# schematicEagle.net
KiCad netlist of a schematic drawn in EAGLE
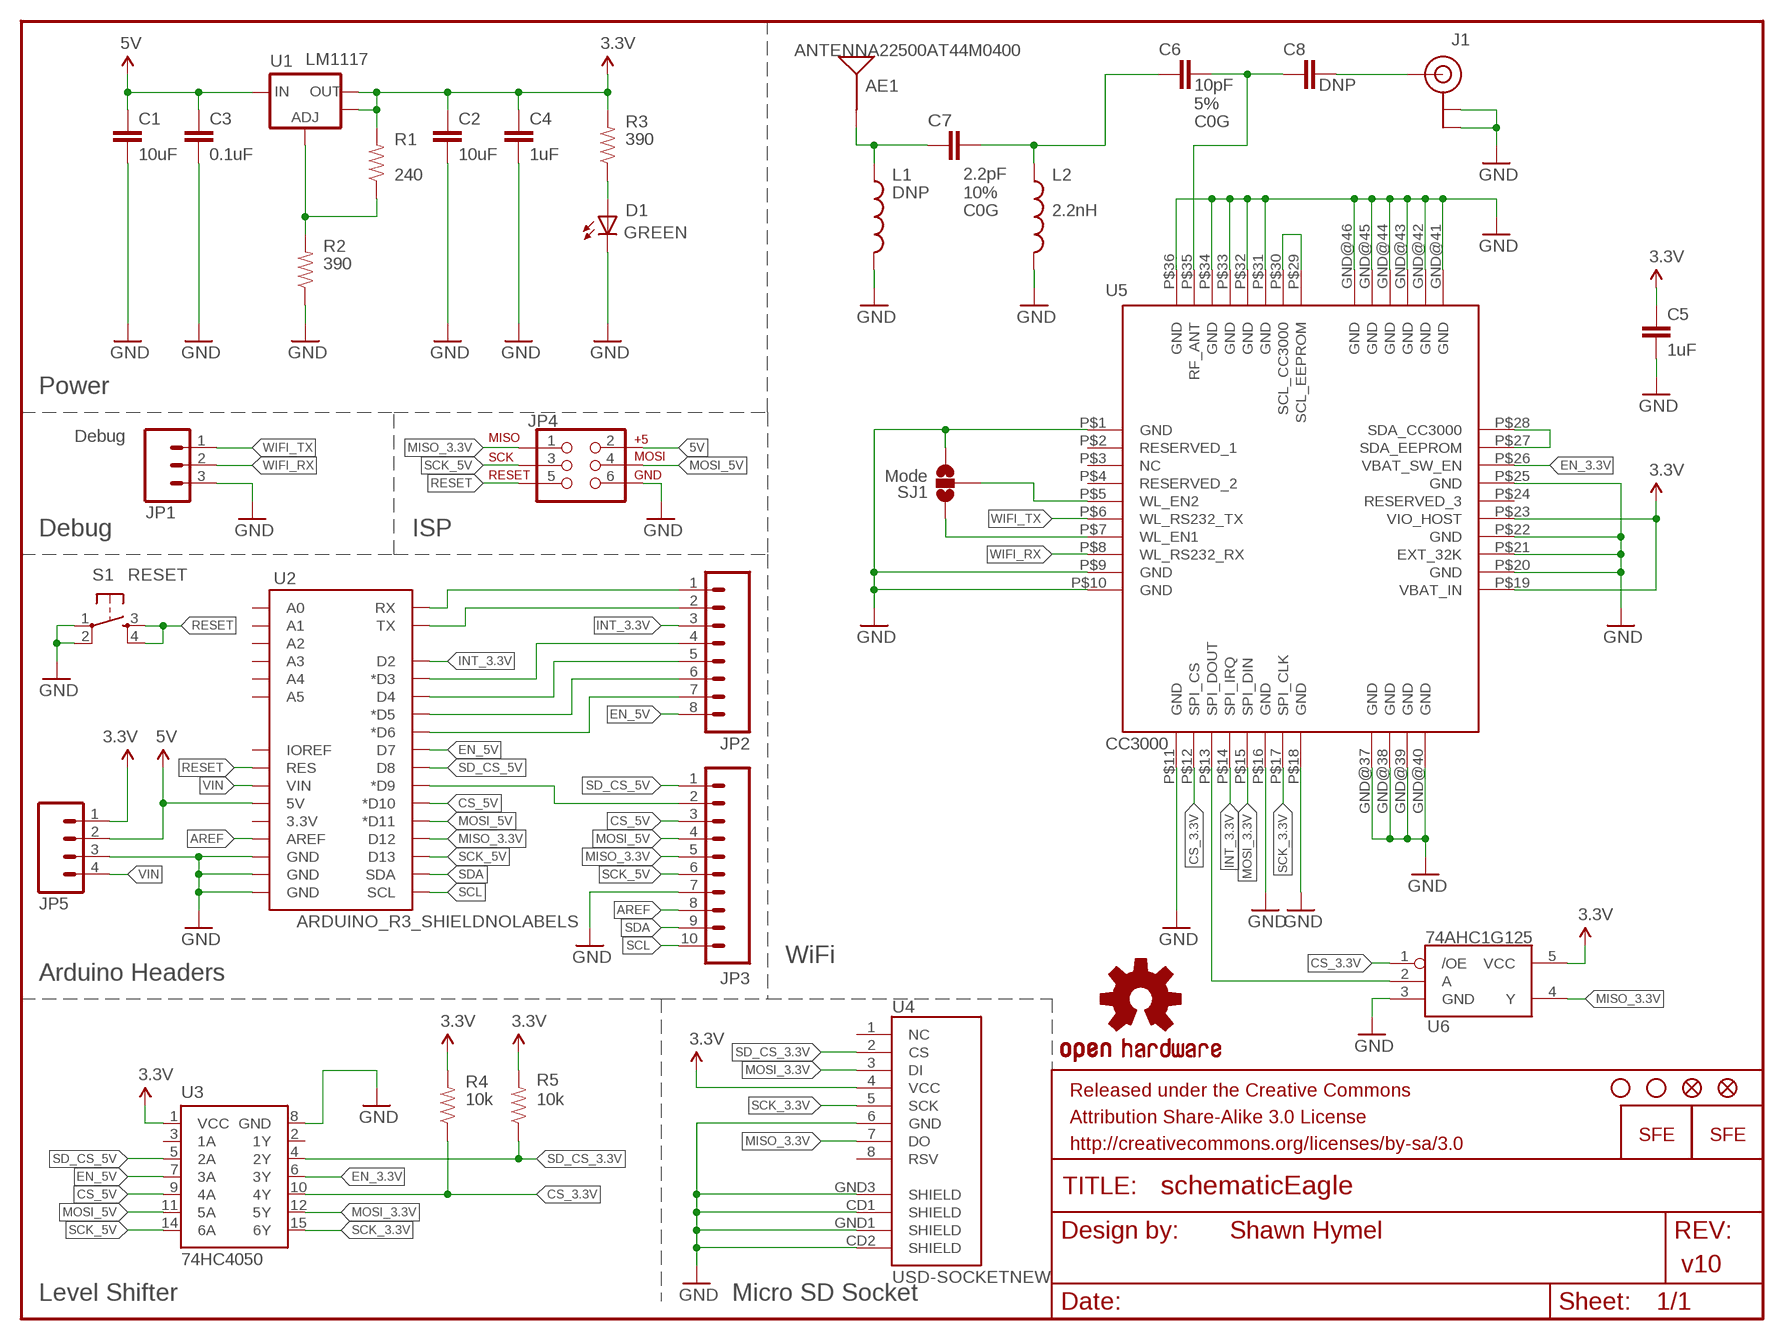
[diagram p0: schematic, sheet 1]

(export (version "E")
  (design (tool "Eeschema 10.0.6"))
  (components
    (comp (ref "AE1")
      (value "ANTENNA22500AT44M0400")
      (footprint "eagle-import:ANTENNA-CHIP_2500AT44M0400")
      (libsource (lib "eagle-import") (part "ANTENNA22500AT44M0400"))
    )
    (comp (ref "C1")
      (value "10uF")
      (footprint "eagle-import:0805")
      (libsource (lib "eagle-import") (part "CAP0805"))
    )
    (comp (ref "C2")
      (value "10uF")
      (footprint "eagle-import:0805")
      (libsource (lib "eagle-import") (part "CAP0805"))
    )
    (comp (ref "C3")
      (value "0.1uF")
      (footprint "eagle-import:0603-CAP")
      (libsource (lib "eagle-import") (part "CAP0603-CAP"))
    )
    (comp (ref "C4")
      (value "1uF")
      (footprint "eagle-import:0805")
      (libsource (lib "eagle-import") (part "CAP0805"))
    )
    (comp (ref "C5")
      (value "1uF")
      (footprint "eagle-import:0805")
      (libsource (lib "eagle-import") (part "CAP0805"))
    )
    (comp (ref "C6")
      (value "10pF")
      (footprint "eagle-import:0603-CAP")
      (fields (field (name "COEFF") "C0G") (field (name "TOL") "5%"))
      (libsource (lib "eagle-import") (part "CAP0603-CAP"))
    )
    (comp (ref "C7")
      (value "2.2pF")
      (footprint "eagle-import:0603-CAP")
      (fields (field (name "COEFF") "C0G") (field (name "TOL") "10%"))
      (libsource (lib "eagle-import") (part "CAP0603-CAP"))
    )
    (comp (ref "C8")
      (value "DNP")
      (footprint "eagle-import:0603-CAP")
      (libsource (lib "eagle-import") (part "CAP0603-CAP"))
    )
    (comp (ref "D1")
      (value "GREEN")
      (footprint "eagle-import:LED-0603")
      (libsource (lib "eagle-import") (part "LED-GREEN0603"))
    )
    (comp (ref "FID1")
      (value "FIDUCIAL1X2")
      (footprint "eagle-import:FIDUCIAL-1X2")
      (libsource (lib "eagle-import") (part "FIDUCIAL1X2"))
    )
    (comp (ref "FID2")
      (value "FIDUCIAL1X2")
      (footprint "eagle-import:FIDUCIAL-1X2")
      (libsource (lib "eagle-import") (part "FIDUCIAL1X2"))
    )
    (comp (ref "FRAME1")
      (value "FRAME-LETTER")
      (footprint "eagle-import:CREATIVE_COMMONS")
      (libsource (lib "eagle-import") (part "FRAME-LETTER"))
    )
    (comp (ref "J1")
      (value "U.FL")
      (footprint "eagle-import:U.FL")
      (libsource (lib "eagle-import") (part "U.FL"))
    )
    (comp (ref "JP1")
      (value "Debug")
      (footprint "eagle-import:1X03")
      (libsource (lib "eagle-import") (part "M03PTH"))
    )
    (comp (ref "JP2")
      (value "M08NO_SILK")
      (footprint "eagle-import:1X08_NO_SILK")
      (libsource (lib "eagle-import") (part "M08NO_SILK"))
    )
    (comp (ref "JP3")
      (value "M10NO_SILK")
      (footprint "eagle-import:1X10_NO_SILK")
      (libsource (lib "eagle-import") (part "M10NO_SILK"))
    )
    (comp (ref "JP4")
      (value "AVR_SPI_PRG_6PTH")
      (footprint "eagle-import:2X3")
      (libsource (lib "eagle-import") (part "AVR_SPI_PRG_6PTH"))
    )
    (comp (ref "JP5")
      (value "M04PTH")
      (footprint "eagle-import:1X04")
      (libsource (lib "eagle-import") (part "M04PTH"))
    )
    (comp (ref "L1")
      (value "DNP")
      (footprint "eagle-import:0603")
      (libsource (lib "eagle-import") (part "INDUCTOR0603"))
    )
    (comp (ref "L2")
      (value "2.2nH")
      (footprint "eagle-import:0603")
      (libsource (lib "eagle-import") (part "INDUCTOR0603"))
    )
    (comp (ref "LOGO1")
      (value "OSHW-LOGOS")
      (footprint "eagle-import:OSHW-LOGO-S")
      (libsource (lib "eagle-import") (part "OSHW-LOGOS"))
    )
    (comp (ref "LOGO2")
      (value "LOGO-SFENEW")
      (footprint "eagle-import:SFE-NEW-WEBLOGO")
      (libsource (lib "eagle-import") (part "LOGO-SFENEW"))
    )
    (comp (ref "LOGO3")
      (value "LOGO-SFESK")
      (footprint "eagle-import:SFE-LOGO-FLAME")
      (libsource (lib "eagle-import") (part "LOGO-SFESK"))
    )
    (comp (ref "R1")
      (value "240")
      (footprint "eagle-import:0603-RES")
      (libsource (lib "eagle-import") (part "RESISTOR0603"))
    )
    (comp (ref "R2")
      (value "390")
      (footprint "eagle-import:0603-RES")
      (libsource (lib "eagle-import") (part "RESISTOR0603"))
    )
    (comp (ref "R3")
      (value "390")
      (footprint "eagle-import:0603-RES")
      (libsource (lib "eagle-import") (part "RESISTOR0603-RES"))
    )
    (comp (ref "R4")
      (value "10k")
      (footprint "eagle-import:0603-RES")
      (libsource (lib "eagle-import") (part "RESISTOR0603-RES"))
    )
    (comp (ref "R5")
      (value "10k")
      (footprint "eagle-import:0603-RES")
      (libsource (lib "eagle-import") (part "RESISTOR0603-RES"))
    )
    (comp (ref "S1")
      (value "RESET")
      (footprint "eagle-import:TACTILE_SWITCH_SMD")
      (libsource (lib "eagle-import") (part "TAC_SWITCHSMD"))
    )
    (comp (ref "SJ1")
      (value "Mode")
      (footprint "eagle-import:SJ_3_PASTE1&2")
      (libsource (lib "eagle-import") (part "SOLDERJUMPER_2WAYPASTE1&2"))
    )
    (comp (ref "STANDOFF1")
      (value "STAND-OFF")
      (footprint "eagle-import:STAND-OFF")
      (libsource (lib "eagle-import") (part "STAND-OFF"))
    )
    (comp (ref "STANDOFF2")
      (value "STAND-OFF")
      (footprint "eagle-import:STAND-OFF")
      (libsource (lib "eagle-import") (part "STAND-OFF"))
    )
    (comp (ref "U1")
      (value "LM1117")
      (footprint "eagle-import:SOT223")
      (libsource (lib "eagle-import") (part "V_REG_LM1117SOT223"))
    )
    (comp (ref "U2")
      (value "ARDUINO_R3_SHIELDNOLABELS")
      (footprint "eagle-import:UNO_R3_SHIELD_NOLABELS")
      (libsource (lib "eagle-import") (part "ARDUINO_R3_SHIELDNOLABELS"))
    )
    (comp (ref "U3")
      (value "74HC4050")
      (footprint "eagle-import:SO016")
      (libsource (lib "eagle-import") (part "HEX_CONVERTER"))
    )
    (comp (ref "U4")
      (value "USD-SOCKETNEW")
      (footprint "eagle-import:MICRO-SD-SOCKET-PP")
      (libsource (lib "eagle-import") (part "USD-SOCKETNEW"))
    )
    (comp (ref "U5")
      (value "CC3000")
      (footprint "eagle-import:QFN-46_CC3000")
      (libsource (lib "eagle-import") (part "CC3000"))
    )
    (comp (ref "U6")
      (value "74AHC1G125")
      (footprint "eagle-import:SOT23-5")
      (libsource (lib "eagle-import") (part "74AHC1G125"))
    )
  )
  (nets
    (net (code "1") (name "3.3V") (class "Default")
      (node (ref "C2") (pin "1") (pinfunction "1_1") (pintype "passive"))
      (node (ref "C4") (pin "1") (pinfunction "1_1") (pintype "passive"))
      (node (ref "C5") (pin "1") (pinfunction "1_1") (pintype "passive"))
      (node (ref "JP5") (pin "1") (pinfunction "1_1") (pintype "passive"))
      (node (ref "R1") (pin "2") (pinfunction "2_2") (pintype "passive"))
      (node (ref "R3") (pin "2") (pinfunction "2_2") (pintype "passive"))
      (node (ref "R4") (pin "2") (pinfunction "2_2") (pintype "passive"))
      (node (ref "R5") (pin "2") (pinfunction "2_2") (pintype "passive"))
      (node (ref "U1") (pin "2") (pinfunction "OUT_2") (pintype "output"))
      (node (ref "U1") (pin "4") (pinfunction "OUT_4") (pintype "output"))
      (node (ref "U3") (pin "1") (pinfunction "VCC_1") (pintype "bidirectional"))
      (node (ref "U4") (pin "4") (pinfunction "VCC_4") (pintype "bidirectional"))
      (node (ref "U5") (pin "P$19") (pinfunction "VBAT_IN_P$19") (pintype "bidirectional"))
      (node (ref "U5") (pin "P$23") (pinfunction "VIO_HOST_P$23") (pintype "bidirectional"))
      (node (ref "U6") (pin "5") (pinfunction "VCC_5") (pintype "bidirectional"))
    )
    (net (code "2") (name "5V") (class "Default")
      (node (ref "C1") (pin "1") (pinfunction "1_1") (pintype "passive"))
      (node (ref "C3") (pin "1") (pinfunction "1_1") (pintype "passive"))
      (node (ref "JP4") (pin "2") (pinfunction "2_2") (pintype "passive"))
      (node (ref "JP5") (pin "2") (pinfunction "2_2") (pintype "passive"))
      (node (ref "U1") (pin "3") (pinfunction "IN_3") (pintype "input"))
      (node (ref "U2") (pin "5V") (pinfunction "5V_5V") (pintype "bidirectional"))
    )
    (net (code "3") (name "AREF") (class "Default")
      (node (ref "JP3") (pin "8") (pinfunction "8_8") (pintype "passive"))
      (node (ref "U2") (pin "AREF") (pinfunction "AREF_AREF") (pintype "bidirectional"))
    )
    (net (code "4") (name "CS_3.3V") (class "Default")
      (node (ref "R4") (pin "1") (pinfunction "1_1") (pintype "passive"))
      (node (ref "U3") (pin "10") (pinfunction "4Y_10") (pintype "bidirectional"))
      (node (ref "U5") (pin "P$12") (pinfunction "SPI_CS_P$12") (pintype "bidirectional"))
      (node (ref "U6") (pin "1") (pinfunction "/OE_1") (pintype "bidirectional"))
    )
    (net (code "5") (name "CS_5V") (class "Default")
      (node (ref "JP3") (pin "3") (pinfunction "3_3") (pintype "passive"))
      (node (ref "U2") (pin "D10") (pinfunction "*D10_D10") (pintype "bidirectional"))
      (node (ref "U3") (pin "9") (pinfunction "4A_9") (pintype "bidirectional"))
    )
    (net (code "6") (name "EN_3.3V") (class "Default")
      (node (ref "U3") (pin "6") (pinfunction "3Y_6") (pintype "bidirectional"))
      (node (ref "U5") (pin "P$26") (pinfunction "VBAT_SW_EN_P$26") (pintype "bidirectional"))
    )
    (net (code "7") (name "EN_5V") (class "Default")
      (node (ref "JP2") (pin "8") (pinfunction "8_8") (pintype "passive"))
      (node (ref "U2") (pin "D7") (pinfunction "D7_D7") (pintype "bidirectional"))
      (node (ref "U3") (pin "7") (pinfunction "3A_7") (pintype "bidirectional"))
    )
    (net (code "8") (name "GND") (class "Default")
      (node (ref "C1") (pin "2") (pinfunction "2_2") (pintype "passive"))
      (node (ref "C2") (pin "2") (pinfunction "2_2") (pintype "passive"))
      (node (ref "C3") (pin "2") (pinfunction "2_2") (pintype "passive"))
      (node (ref "C4") (pin "2") (pinfunction "2_2") (pintype "passive"))
      (node (ref "C5") (pin "2") (pinfunction "2_2") (pintype "passive"))
      (node (ref "D1") (pin "C") (pinfunction "C_C") (pintype "passive"))
      (node (ref "J1") (pin "P$1") (pinfunction "GND_P$1") (pintype "bidirectional"))
      (node (ref "J1") (pin "P$2") (pinfunction "GND_P$2") (pintype "bidirectional"))
      (node (ref "JP1") (pin "3") (pinfunction "3_3") (pintype "passive"))
      (node (ref "JP3") (pin "7") (pinfunction "7_7") (pintype "passive"))
      (node (ref "JP4") (pin "6") (pinfunction "6_6") (pintype "passive"))
      (node (ref "JP5") (pin "3") (pinfunction "3_3") (pintype "passive"))
      (node (ref "L1") (pin "2") (pinfunction "2_2") (pintype "passive"))
      (node (ref "L2") (pin "2") (pinfunction "2_2") (pintype "passive"))
      (node (ref "R2") (pin "1") (pinfunction "1_1") (pintype "passive"))
      (node (ref "S1") (pin "1") (pinfunction "1_1") (pintype "passive"))
      (node (ref "S1") (pin "2") (pinfunction "2_2") (pintype "passive"))
      (node (ref "SJ1") (pin "3") (pinfunction "3_3") (pintype "passive"))
      (node (ref "U2") (pin "GND@0") (pinfunction "GND_GND@0") (pintype "bidirectional"))
      (node (ref "U2") (pin "GND@1") (pinfunction "GND_GND@1") (pintype "bidirectional"))
      (node (ref "U2") (pin "GND@2") (pinfunction "GND_GND@2") (pintype "bidirectional"))
      (node (ref "U3") (pin "8") (pinfunction "GND_8") (pintype "bidirectional"))
      (node (ref "U4") (pin "6") (pinfunction "GND_6") (pintype "bidirectional"))
      (node (ref "U4") (pin "CD1") (pinfunction "SHIELD_CD1") (pintype "bidirectional"))
      (node (ref "U4") (pin "CD2") (pinfunction "SHIELD_CD2") (pintype "bidirectional"))
      (node (ref "U4") (pin "GND1") (pinfunction "SHIELD_GND1") (pintype "bidirectional"))
      (node (ref "U4") (pin "GND3") (pinfunction "SHIELD_GND3") (pintype "bidirectional"))
      (node (ref "U5") (pin "GND@37") (pinfunction "GND_GND@37") (pintype "bidirectional"))
      (node (ref "U5") (pin "GND@38") (pinfunction "GND_GND@38") (pintype "bidirectional"))
      (node (ref "U5") (pin "GND@39") (pinfunction "GND_GND@39") (pintype "bidirectional"))
      (node (ref "U5") (pin "GND@40") (pinfunction "GND_GND@40") (pintype "bidirectional"))
      (node (ref "U5") (pin "GND@41") (pinfunction "GND_GND@41") (pintype "bidirectional"))
      (node (ref "U5") (pin "GND@42") (pinfunction "GND_GND@42") (pintype "bidirectional"))
      (node (ref "U5") (pin "GND@43") (pinfunction "GND_GND@43") (pintype "bidirectional"))
      (node (ref "U5") (pin "GND@44") (pinfunction "GND_GND@44") (pintype "bidirectional"))
      (node (ref "U5") (pin "GND@45") (pinfunction "GND_GND@45") (pintype "bidirectional"))
      (node (ref "U5") (pin "GND@46") (pinfunction "GND_GND@46") (pintype "bidirectional"))
      (node (ref "U5") (pin "P$1") (pinfunction "GND_P$1") (pintype "bidirectional"))
      (node (ref "U5") (pin "P$10") (pinfunction "GND_P$10") (pintype "bidirectional"))
      (node (ref "U5") (pin "P$11") (pinfunction "GND_P$11") (pintype "bidirectional"))
      (node (ref "U5") (pin "P$16") (pinfunction "GND_P$16") (pintype "bidirectional"))
      (node (ref "U5") (pin "P$18") (pinfunction "GND_P$18") (pintype "bidirectional"))
      (node (ref "U5") (pin "P$20") (pinfunction "GND_P$20") (pintype "bidirectional"))
      (node (ref "U5") (pin "P$21") (pinfunction "EXT_32K_P$21") (pintype "bidirectional"))
      (node (ref "U5") (pin "P$22") (pinfunction "GND_P$22") (pintype "bidirectional"))
      (node (ref "U5") (pin "P$25") (pinfunction "GND_P$25") (pintype "bidirectional"))
      (node (ref "U5") (pin "P$31") (pinfunction "GND_P$31") (pintype "bidirectional"))
      (node (ref "U5") (pin "P$32") (pinfunction "GND_P$32") (pintype "bidirectional"))
      (node (ref "U5") (pin "P$33") (pinfunction "GND_P$33") (pintype "bidirectional"))
      (node (ref "U5") (pin "P$34") (pinfunction "GND_P$34") (pintype "bidirectional"))
      (node (ref "U5") (pin "P$36") (pinfunction "GND_P$36") (pintype "bidirectional"))
      (node (ref "U5") (pin "P$9") (pinfunction "GND_P$9") (pintype "bidirectional"))
      (node (ref "U6") (pin "3") (pinfunction "GND_3") (pintype "bidirectional"))
    )
    (net (code "9") (name "INT_3.3V") (class "Default")
      (node (ref "JP2") (pin "3") (pinfunction "3_3") (pintype "passive"))
      (node (ref "U2") (pin "D2") (pinfunction "D2_D2") (pintype "bidirectional"))
      (node (ref "U5") (pin "P$14") (pinfunction "SPI_IRQ_P$14") (pintype "bidirectional"))
    )
    (net (code "10") (name "MISO_3.3V") (class "Default")
      (node (ref "JP3") (pin "5") (pinfunction "5_5") (pintype "passive"))
      (node (ref "JP4") (pin "1") (pinfunction "1_1") (pintype "passive"))
      (node (ref "U2") (pin "D12") (pinfunction "D12_D12") (pintype "bidirectional"))
      (node (ref "U4") (pin "7") (pinfunction "DO_7") (pintype "bidirectional"))
      (node (ref "U6") (pin "4") (pinfunction "Y_4") (pintype "bidirectional"))
    )
    (net (code "11") (name "MOSI_3.3V") (class "Default")
      (node (ref "U3") (pin "12") (pinfunction "5Y_12") (pintype "bidirectional"))
      (node (ref "U4") (pin "3") (pinfunction "DI_3") (pintype "bidirectional"))
      (node (ref "U5") (pin "P$15") (pinfunction "SPI_DIN_P$15") (pintype "bidirectional"))
    )
    (net (code "12") (name "MOSI_5V") (class "Default")
      (node (ref "JP3") (pin "4") (pinfunction "4_4") (pintype "passive"))
      (node (ref "JP4") (pin "4") (pinfunction "4_4") (pintype "passive"))
      (node (ref "U2") (pin "D11") (pinfunction "*D11_D11") (pintype "bidirectional"))
      (node (ref "U3") (pin "11") (pinfunction "5A_11") (pintype "bidirectional"))
    )
    (net (code "13") (name "Net-(AE1-SIGNAL)") (class "Default")
      (node (ref "AE1") (pin "FEED") (pinfunction "SIGNAL_FEED") (pintype "bidirectional"))
      (node (ref "C7") (pin "1") (pinfunction "1_1") (pintype "passive"))
      (node (ref "L1") (pin "1") (pinfunction "1_1") (pintype "passive"))
    )
    (net (code "14") (name "Net-(C6-Pad1)") (class "Default")
      (node (ref "C6") (pin "1") (pinfunction "1_1") (pintype "passive"))
      (node (ref "C7") (pin "2") (pinfunction "2_2") (pintype "passive"))
      (node (ref "L2") (pin "1") (pinfunction "1_1") (pintype "passive"))
    )
    (net (code "15") (name "Net-(D1-PadA)") (class "Default")
      (node (ref "D1") (pin "A") (pinfunction "A_A") (pintype "passive"))
      (node (ref "R3") (pin "1") (pinfunction "1_1") (pintype "passive"))
    )
    (net (code "16") (name "Net-(J1-SIGNAL)") (class "Default")
      (node (ref "C8") (pin "2") (pinfunction "2_2") (pintype "passive"))
      (node (ref "J1") (pin "P$3") (pinfunction "SIGNAL_P$3") (pintype "bidirectional"))
    )
    (net (code "17") (name "Net-(JP2-Pad1)") (class "Default")
      (node (ref "JP2") (pin "1") (pinfunction "1_1") (pintype "passive"))
      (node (ref "U2") (pin "RX") (pinfunction "RX_RX") (pintype "bidirectional"))
    )
    (net (code "18") (name "Net-(JP2-Pad2)") (class "Default")
      (node (ref "JP2") (pin "2") (pinfunction "2_2") (pintype "passive"))
      (node (ref "U2") (pin "TX") (pinfunction "TX_TX") (pintype "bidirectional"))
    )
    (net (code "19") (name "Net-(JP2-Pad5)") (class "Default")
      (node (ref "JP2") (pin "5") (pinfunction "5_5") (pintype "passive"))
      (node (ref "U2") (pin "D4") (pinfunction "D4_D4") (pintype "bidirectional"))
    )
    (net (code "20") (name "Net-(U1-ADJ)") (class "Default")
      (node (ref "R1") (pin "1") (pinfunction "1_1") (pintype "passive"))
      (node (ref "R2") (pin "2") (pinfunction "2_2") (pintype "passive"))
      (node (ref "U1") (pin "1") (pinfunction "ADJ_1") (pintype "input"))
    )
    (net (code "21") (name "Net-(U2-*D3)") (class "Default")
      (node (ref "JP2") (pin "4") (pinfunction "4_4") (pintype "passive"))
      (node (ref "U2") (pin "D3") (pinfunction "*D3_D3") (pintype "bidirectional"))
    )
    (net (code "22") (name "Net-(U2-*D5)") (class "Default")
      (node (ref "JP2") (pin "6") (pinfunction "6_6") (pintype "passive"))
      (node (ref "U2") (pin "D5") (pinfunction "*D5_D5") (pintype "bidirectional"))
    )
    (net (code "23") (name "Net-(U2-*D6)") (class "Default")
      (node (ref "JP2") (pin "7") (pinfunction "7_7") (pintype "passive"))
      (node (ref "U2") (pin "D6") (pinfunction "*D6_D6") (pintype "bidirectional"))
    )
    (net (code "24") (name "Net-(U2-*D9)") (class "Default")
      (node (ref "JP3") (pin "2") (pinfunction "2_2") (pintype "passive"))
      (node (ref "U2") (pin "D9") (pinfunction "*D9_D9") (pintype "bidirectional"))
    )
    (net (code "25") (name "Net-(U5-RF_ANT)") (class "Default")
      (node (ref "C6") (pin "2") (pinfunction "2_2") (pintype "passive"))
      (node (ref "C8") (pin "1") (pinfunction "1_1") (pintype "passive"))
      (node (ref "U5") (pin "P$35") (pinfunction "RF_ANT_P$35") (pintype "bidirectional"))
    )
    (net (code "26") (name "Net-(U5-SCL_CC3000)") (class "Default")
      (node (ref "U5") (pin "P$29") (pinfunction "SCL_EEPROM_P$29") (pintype "bidirectional"))
      (node (ref "U5") (pin "P$30") (pinfunction "SCL_CC3000_P$30") (pintype "bidirectional"))
    )
    (net (code "27") (name "Net-(U5-SDA_CC3000)") (class "Default")
      (node (ref "U5") (pin "P$27") (pinfunction "SDA_EEPROM_P$27") (pintype "bidirectional"))
      (node (ref "U5") (pin "P$28") (pinfunction "SDA_CC3000_P$28") (pintype "bidirectional"))
    )
    (net (code "28") (name "Net-(U5-SPI_DOUT)") (class "Default")
      (node (ref "U5") (pin "P$13") (pinfunction "SPI_DOUT_P$13") (pintype "bidirectional"))
      (node (ref "U6") (pin "2") (pinfunction "A_2") (pintype "bidirectional"))
    )
    (net (code "29") (name "Net-(U5-WL_EN1)") (class "Default")
      (node (ref "SJ1") (pin "1") (pinfunction "1_1") (pintype "passive"))
      (node (ref "U5") (pin "P$7") (pinfunction "WL_EN1_P$7") (pintype "bidirectional"))
    )
    (net (code "30") (name "Net-(U5-WL_EN2)") (class "Default")
      (node (ref "SJ1") (pin "2") (pinfunction "2_2") (pintype "passive"))
      (node (ref "U5") (pin "P$5") (pinfunction "WL_EN2_P$5") (pintype "bidirectional"))
    )
    (net (code "31") (name "RESET") (class "Default")
      (node (ref "JP4") (pin "5") (pinfunction "5_5") (pintype "passive"))
      (node (ref "S1") (pin "3") (pinfunction "3_3") (pintype "passive"))
      (node (ref "S1") (pin "4") (pinfunction "4_4") (pintype "passive"))
      (node (ref "U2") (pin "RES") (pinfunction "RES_RES") (pintype "bidirectional"))
    )
    (net (code "32") (name "SCK_3.3V") (class "Default")
      (node (ref "U3") (pin "15") (pinfunction "6Y_15") (pintype "bidirectional"))
      (node (ref "U4") (pin "5") (pinfunction "SCK_5") (pintype "bidirectional"))
      (node (ref "U5") (pin "P$17") (pinfunction "SPI_CLK_P$17") (pintype "bidirectional"))
    )
    (net (code "33") (name "SCK_5V") (class "Default")
      (node (ref "JP3") (pin "6") (pinfunction "6_6") (pintype "passive"))
      (node (ref "JP4") (pin "3") (pinfunction "3_3") (pintype "passive"))
      (node (ref "U2") (pin "D13") (pinfunction "D13_D13") (pintype "bidirectional"))
      (node (ref "U3") (pin "14") (pinfunction "6A_14") (pintype "bidirectional"))
    )
    (net (code "34") (name "SCL") (class "Default")
      (node (ref "JP3") (pin "10") (pinfunction "10_10") (pintype "passive"))
      (node (ref "U2") (pin "SCL") (pinfunction "SCL_SCL") (pintype "bidirectional"))
    )
    (net (code "35") (name "SDA") (class "Default")
      (node (ref "JP3") (pin "9") (pinfunction "9_9") (pintype "passive"))
      (node (ref "U2") (pin "SDA") (pinfunction "SDA_SDA") (pintype "bidirectional"))
    )
    (net (code "36") (name "SD_CS_3.3V") (class "Default")
      (node (ref "R5") (pin "1") (pinfunction "1_1") (pintype "passive"))
      (node (ref "U3") (pin "4") (pinfunction "2Y_4") (pintype "bidirectional"))
      (node (ref "U4") (pin "2") (pinfunction "CS_2") (pintype "bidirectional"))
    )
    (net (code "37") (name "SD_CS_5V") (class "Default")
      (node (ref "JP3") (pin "1") (pinfunction "1_1") (pintype "passive"))
      (node (ref "U2") (pin "D8") (pinfunction "D8_D8") (pintype "bidirectional"))
      (node (ref "U3") (pin "5") (pinfunction "2A_5") (pintype "bidirectional"))
    )
    (net (code "38") (name "VIN") (class "Default")
      (node (ref "JP5") (pin "4") (pinfunction "4_4") (pintype "passive"))
      (node (ref "U2") (pin "VIN") (pinfunction "VIN_VIN") (pintype "bidirectional"))
    )
    (net (code "39") (name "WIFI_RX") (class "Default")
      (node (ref "JP1") (pin "2") (pinfunction "2_2") (pintype "passive"))
      (node (ref "U5") (pin "P$8") (pinfunction "WL_RS232_RX_P$8") (pintype "bidirectional"))
    )
    (net (code "40") (name "WIFI_TX") (class "Default")
      (node (ref "JP1") (pin "1") (pinfunction "1_1") (pintype "passive"))
      (node (ref "U5") (pin "P$6") (pinfunction "WL_RS232_TX_P$6") (pintype "bidirectional"))
    )
    (net (code "41") (name "unconnected-(U2-Pad3.3V)") (class "Default")
      (node (ref "U2") (pin "3.3V") (pinfunction "3.3V_3.3V") (pintype "bidirectional"))
    )
    (net (code "42") (name "unconnected-(U2-PadA0)") (class "Default")
      (node (ref "U2") (pin "A0") (pinfunction "A0_A0") (pintype "bidirectional"))
    )
    (net (code "43") (name "unconnected-(U2-PadA1)") (class "Default")
      (node (ref "U2") (pin "A1") (pinfunction "A1_A1") (pintype "bidirectional"))
    )
    (net (code "44") (name "unconnected-(U2-PadA2)") (class "Default")
      (node (ref "U2") (pin "A2") (pinfunction "A2_A2") (pintype "bidirectional"))
    )
    (net (code "45") (name "unconnected-(U2-PadA3)") (class "Default")
      (node (ref "U2") (pin "A3") (pinfunction "A3_A3") (pintype "bidirectional"))
    )
    (net (code "46") (name "unconnected-(U2-PadA4)") (class "Default")
      (node (ref "U2") (pin "A4") (pinfunction "A4_A4") (pintype "bidirectional"))
    )
    (net (code "47") (name "unconnected-(U2-PadA5)") (class "Default")
      (node (ref "U2") (pin "A5") (pinfunction "A5_A5") (pintype "bidirectional"))
    )
    (net (code "48") (name "unconnected-(U2-PadIOREF)") (class "Default")
      (node (ref "U2") (pin "IOREF") (pinfunction "IOREF_IOREF") (pintype "bidirectional"))
    )
    (net (code "49") (name "unconnected-(U3-1A-Pad3)") (class "Default")
      (node (ref "U3") (pin "3") (pinfunction "1A_3") (pintype "bidirectional"))
    )
    (net (code "50") (name "unconnected-(U3-1Y-Pad2)") (class "Default")
      (node (ref "U3") (pin "2") (pinfunction "1Y_2") (pintype "bidirectional"))
    )
    (net (code "51") (name "unconnected-(U4-NC-Pad1)") (class "Default")
      (node (ref "U4") (pin "1") (pinfunction "NC_1") (pintype "bidirectional"))
    )
    (net (code "52") (name "unconnected-(U4-RSV-Pad8)") (class "Default")
      (node (ref "U4") (pin "8") (pinfunction "RSV_8") (pintype "bidirectional"))
    )
    (net (code "53") (name "unconnected-(U5-NC-PadP$3)") (class "Default")
      (node (ref "U5") (pin "P$3") (pinfunction "NC_P$3") (pintype "bidirectional"))
    )
    (net (code "54") (name "unconnected-(U5-RESERVED_1-PadP$2)") (class "Default")
      (node (ref "U5") (pin "P$2") (pinfunction "RESERVED_1_P$2") (pintype "bidirectional"))
    )
    (net (code "55") (name "unconnected-(U5-RESERVED_2-PadP$4)") (class "Default")
      (node (ref "U5") (pin "P$4") (pinfunction "RESERVED_2_P$4") (pintype "bidirectional"))
    )
    (net (code "56") (name "unconnected-(U5-RESERVED_3-PadP$24)") (class "Default")
      (node (ref "U5") (pin "P$24") (pinfunction "RESERVED_3_P$24") (pintype "bidirectional"))
    )
  )
)
